# Sheet2.net
KiCad netlist of a schematic drawn in Altium Designer
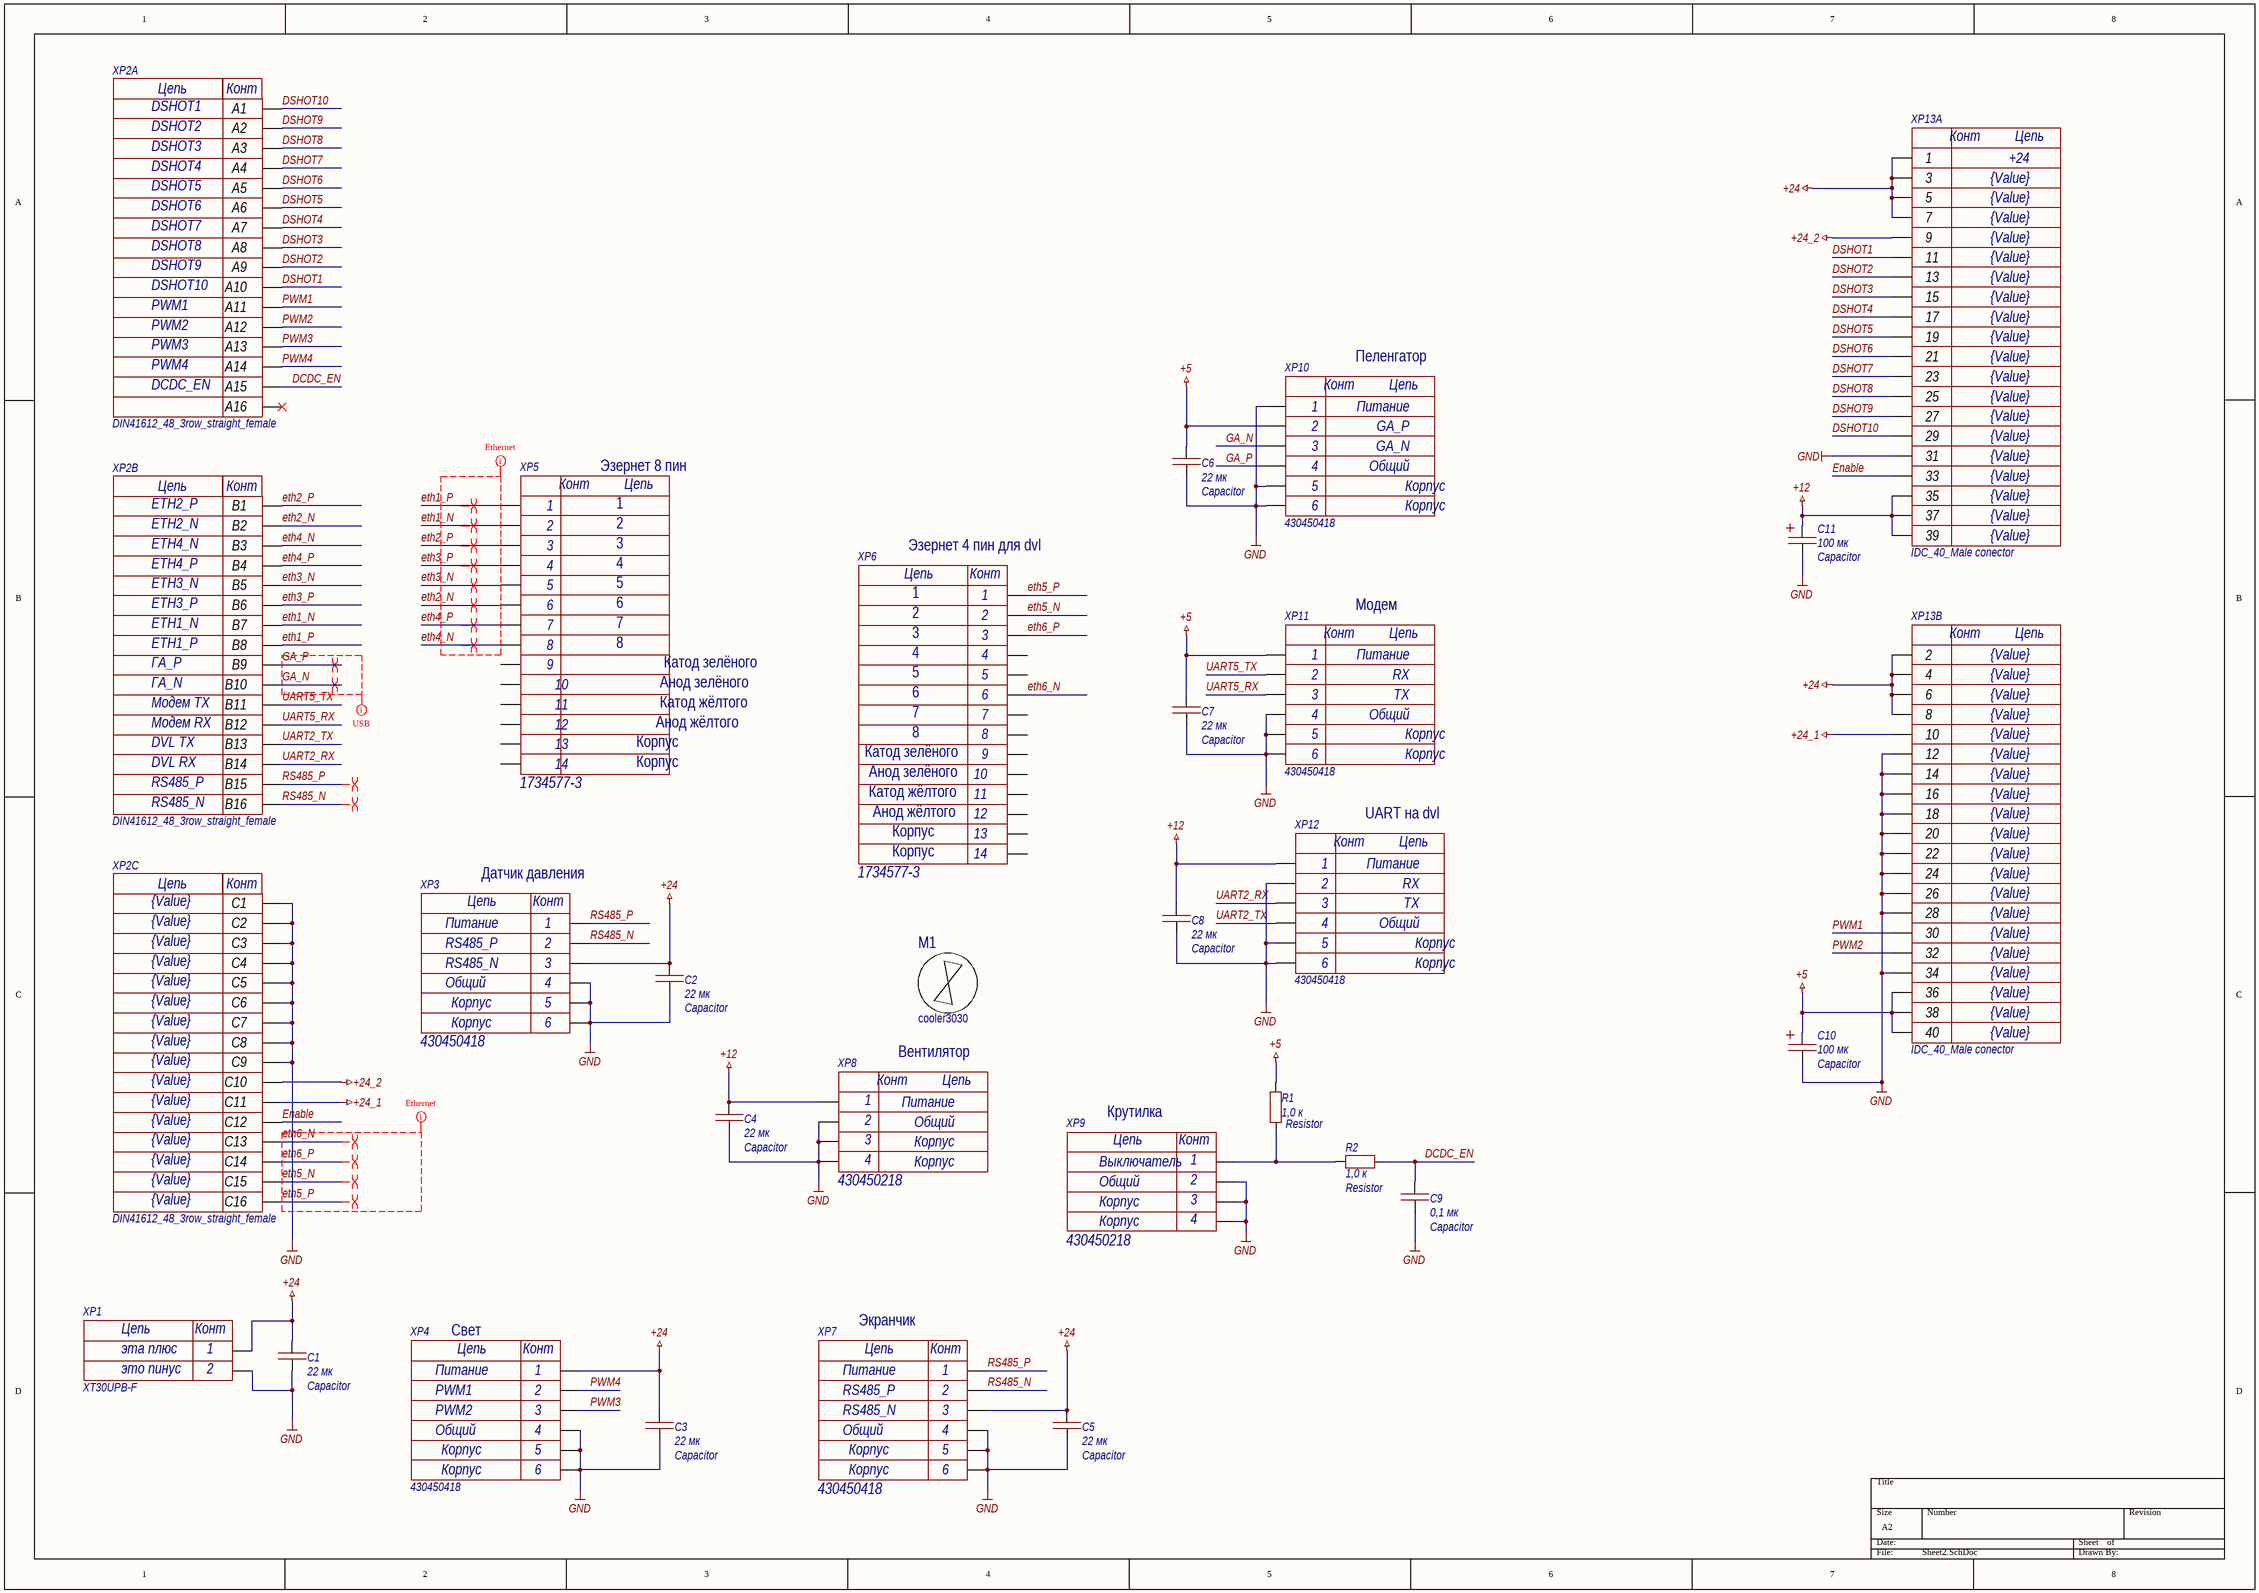
[diagram p0: Sheet2.SchDoc]

(export (version "E")
  (design (tool "Eeschema 10.0.6"))
  (components
    (comp (ref "C1")
      (value "Capacitor")
      (footprint "1210C")
      (description "Конденсатор 1210C ёмкостью 22 мк 10%, 25 В, X7R")
      (fields
        (field (name "ALTIUM_VALUE") "22 мк")
        (field (name "PART NUMBER") "Capacitor_22u_10_25V_X7R_1210C")
        (field (name "TOLERANCE") "10%")
      )
      (libsource (lib "Hydrolib") (part "Capacitor"))
    )
    (comp (ref "C2")
      (value "Capacitor")
      (footprint "1210C")
      (description "Конденсатор 1210C ёмкостью 22 мк 10%, 25 В, X7R")
      (fields
        (field (name "ALTIUM_VALUE") "22 мк")
        (field (name "PART NUMBER") "Capacitor_22u_10_25V_X7R_1210C")
        (field (name "TOLERANCE") "10%")
      )
      (libsource (lib "Hydrolib") (part "Capacitor"))
    )
    (comp (ref "C3")
      (value "Capacitor")
      (footprint "1210C")
      (description "Конденсатор 1210C ёмкостью 22 мк 10%, 25 В, X7R")
      (fields
        (field (name "ALTIUM_VALUE") "22 мк")
        (field (name "PART NUMBER") "Capacitor_22u_10_25V_X7R_1210C")
        (field (name "TOLERANCE") "10%")
      )
      (libsource (lib "Hydrolib") (part "Capacitor"))
    )
    (comp (ref "C4")
      (value "Capacitor")
      (footprint "1210C")
      (description "Конденсатор 1210C ёмкостью 22 мк 10%, 25 В, X7R")
      (fields
        (field (name "ALTIUM_VALUE") "22 мк")
        (field (name "PART NUMBER") "Capacitor_22u_10_25V_X7R_1210C")
        (field (name "TOLERANCE") "10%")
      )
      (libsource (lib "Hydrolib") (part "Capacitor"))
    )
    (comp (ref "C5")
      (value "Capacitor")
      (footprint "1210C")
      (description "Конденсатор 1210C ёмкостью 22 мк 10%, 25 В, X7R")
      (fields
        (field (name "ALTIUM_VALUE") "22 мк")
        (field (name "PART NUMBER") "Capacitor_22u_10_25V_X7R_1210C")
        (field (name "TOLERANCE") "10%")
      )
      (libsource (lib "Hydrolib") (part "Capacitor"))
    )
    (comp (ref "C6")
      (value "Capacitor")
      (footprint "1210C")
      (description "Конденсатор 1210C ёмкостью 22 мк 10%, 25 В, X7R")
      (fields
        (field (name "ALTIUM_VALUE") "22 мк")
        (field (name "PART NUMBER") "Capacitor_22u_10_25V_X7R_1210C")
        (field (name "TOLERANCE") "10%")
      )
      (libsource (lib "Hydrolib") (part "Capacitor"))
    )
    (comp (ref "C7")
      (value "Capacitor")
      (footprint "1210C")
      (description "Конденсатор 1210C ёмкостью 22 мк 10%, 25 В, X7R")
      (fields
        (field (name "ALTIUM_VALUE") "22 мк")
        (field (name "PART NUMBER") "Capacitor_22u_10_25V_X7R_1210C")
        (field (name "TOLERANCE") "10%")
      )
      (libsource (lib "Hydrolib") (part "Capacitor"))
    )
    (comp (ref "C8")
      (value "Capacitor")
      (footprint "1210C")
      (description "Конденсатор 1210C ёмкостью 22 мк 10%, 25 В, X7R")
      (fields
        (field (name "ALTIUM_VALUE") "22 мк")
        (field (name "PART NUMBER") "Capacitor_22u_10_25V_X7R_1210C")
        (field (name "TOLERANCE") "10%")
      )
      (libsource (lib "Hydrolib") (part "Capacitor"))
    )
    (comp (ref "C9")
      (value "Capacitor")
      (footprint "0603C")
      (description "Конденсатор 0603C ёмкостью 0,1 мк 10%, 50 В, X7R")
      (fields
        (field (name "ALTIUM_VALUE") "0,1 мк")
        (field (name "PART NUMBER") "Capacitor_0,1u_10_50V_X7R_0603C")
        (field (name "TOLERANCE") "10%")
      )
      (libsource (lib "Hydrolib") (part "Capacitor"))
    )
    (comp (ref "C10")
      (value "Capacitor")
      (footprint "ECAP_SMD_6,6x6,6")
      (description "Конденсатор алюминиевый электролитический 100мкФ 35В 20% SMD 6,6x6,6 мм")
      (fields
        (field (name "ALTIUM_VALUE") "100 мк")
        (field (name "PART NUMBER") "JCK1V101")
        (field (name "TOLERANCE") "20")
      )
      (libsource (lib "Hydrolib") (part "Capacitor_polar"))
    )
    (comp (ref "C11")
      (value "Capacitor")
      (footprint "ECAP_SMD_6,6x6,6")
      (description "Конденсатор алюминиевый электролитический 100мкФ 35В 20% SMD 6,6x6,6 мм")
      (fields
        (field (name "ALTIUM_VALUE") "100 мк")
        (field (name "PART NUMBER") "JCK1V101")
        (field (name "TOLERANCE") "20")
      )
      (libsource (lib "Hydrolib") (part "Capacitor_polar"))
    )
    (comp (ref "M1")
      (value "cooler3030")
      (footprint "cooler3030")
      (description "вентилятор 30*30 с дыркой на плате")
      (libsource (lib "Hydrolib") (part "cooler4040"))
    )
    (comp (ref "R1")
      (value "Resistor")
      (footprint "0603R")
      (description "Резистор номиналом 1,0 кОм 1%")
      (fields
        (field (name "ALTIUM_VALUE") "1,0 к")
        (field (name "PART NUMBER") "Resistor_1.0k_1_0603")
        (field (name "TOLERANCE") "1%")
      )
      (libsource (lib "Hydrolib") (part "Resistor"))
    )
    (comp (ref "R2")
      (value "Resistor")
      (footprint "0603R")
      (description "Резистор номиналом 1,0 кОм 1%")
      (fields
        (field (name "ALTIUM_VALUE") "1,0 к")
        (field (name "PART NUMBER") "Resistor_1.0k_1_0603")
        (field (name "TOLERANCE") "1%")
      )
      (libsource (lib "") (part "Resistor_1"))
    )
    (comp (ref "XP1")
      (value "XT30UPB-F")
      (footprint "XT30UPB-F")
      (description "30 А (15 продолжительно), прямая мать")
      (fields (field (name "VALUE2") "это пинус") (field (name "VALUE1") "эта плюс"))
      (libsource (lib "Hydrolib") (part "Polar_Conn"))
    )
    (comp (ref "XP2")
      (value "DIN41612_48_3row_straight_female")
      (footprint "DIN41612_48_3row_straight_female")
      (fields
        (field (name "PARAMETER 14") "DCDC_EN")
        (field (name "PARAMETER 16") "{Value}")
        (field (name "PARAMETER 15") "PWM4")
        (field (name "PARAMETER 12") "DSHOT7")
        (field (name "PARAMETER 13") "DSHOT5")
        (field (name "PARAMETER 11") "DSHOT6")
        (field (name "PARAMETER 10") "DSHOT4")
        (field (name "PARAMETER 9") "DSHOT3")
        (field (name "PARAMETER 8") "DSHOT2")
        (field (name "PARAMETER 5") "DSHOT1")
        (field (name "PARAMETER 6") "PWM2")
        (field (name "PARAMETER 7") "PWM3")
        (field (name "PARAMETER 4") "DSHOT10")
        (field (name "PARAMETER 3") "DSHOT9")
        (field (name "PARAMETER 2") "DSHOT8")
        (field (name "PARAMETER 1") "PWM1")
      )
      (libsource (lib "Hydrolib") (part "Conn_48pin_3row"))
    )
    (comp (ref "XP3")
      (value "430450418")
      (footprint "MOLEX_430450418")
      (description "Разъем типа провод-плата, 3 мм, 4 контакт(-ов), Штыревой Разъем, для поверностного монтажа")
      (fields
        (field (name "VALUE1") "Питание")
        (field (name "VALUE2") "RS485_P")
        (field (name "VALUE3") "RS485_N")
        (field (name "VALUE4") "Общий")
        (field (name "PART NUMBER") "Molex_430450418")
      )
      (libsource (lib "Hydrolib") (part "Molex_430450415"))
    )
    (comp (ref "XP4")
      (value "430450418")
      (footprint "MOLEX_430450418")
      (description "Разъем типа провод-плата, 3 мм, 4 контакт(-ов), Штыревой Разъем, для поверностного монтажа")
      (fields
        (field (name "VALUE1") "Питание")
        (field (name "VALUE2") "PWM1")
        (field (name "VALUE3") "PWM2")
        (field (name "VALUE4") "Общий")
        (field (name "PART NUMBER") "Molex_430450418")
      )
      (libsource (lib "Hydrolib") (part "Molex_430450415"))
    )
    (comp (ref "XP5")
      (value "1734577-3")
      (footprint "1-1734577-3-rj45-8p8c")
      (description "Модульный разъем, Cat3, RJ45, Гнездо, 8 контакт(-ов), 8 вывод(-ов), 1 порт(-ов)")
      (fields (field (name "PART NUMBER") "1-1734577-3-rj45-8p8c"))
      (libsource (lib "") (part "1-1734577-3-rj45-8p8c_1"))
    )
    (comp (ref "XP6")
      (value "1734577-3")
      (footprint "1-1734577-3-rj45-8p8c")
      (description "Модульный разъем, Cat3, RJ45, Гнездо, 8 контакт(-ов), 8 вывод(-ов), 1 порт(-ов)")
      (fields (field (name "PART NUMBER") "1-1734577-3-rj45-8p8c"))
      (libsource (lib "Hydrolib") (part "1-1734577-3-rj45-8p8c"))
    )
    (comp (ref "XP7")
      (value "430450418")
      (footprint "MOLEX_430450418")
      (description "Разъем типа провод-плата, 3 мм, 4 контакт(-ов), Штыревой Разъем, для поверностного монтажа")
      (fields
        (field (name "VALUE1") "Питание")
        (field (name "VALUE2") "RS485_P")
        (field (name "VALUE3") "RS485_N")
        (field (name "VALUE4") "Общий")
        (field (name "PART NUMBER") "Molex_430450418")
      )
      (libsource (lib "Hydrolib") (part "Molex_430450415"))
    )
    (comp (ref "XP8")
      (value "430450218")
      (footprint "Molex_430450218")
      (fields
        (field (name "VALUE3") "Корпус")
        (field (name "VALUE2") "Общий")
        (field (name "VALUE4") "Корпус")
        (field (name "VALUE1") "Питание")
        (field (name "PART NUMBER") "Molex_430450218")
      )
      (libsource (lib "Hydrolib") (part "Molex_430450218"))
    )
    (comp (ref "XP9")
      (value "430450218")
      (footprint "Molex_430450218")
      (fields
        (field (name "VALUE3") "Корпус")
        (field (name "VALUE2") "Общий")
        (field (name "VALUE4") "Корпус")
        (field (name "VALUE1") "Выключатель")
        (field (name "PART NUMBER") "Molex_430450218")
      )
      (libsource (lib "Hydrolib") (part "Molex_430450218"))
    )
    (comp (ref "XP10")
      (value "430450418")
      (footprint "MOLEX_430450418")
      (description "Разъем типа провод-плата, 3 мм, 4 контакт(-ов), Штыревой Разъем, для поверностного монтажа")
      (fields
        (field (name "VALUE1") "Питание")
        (field (name "VALUE2") "GA_P")
        (field (name "VALUE3") "GA_N")
        (field (name "VALUE4") "Общий")
        (field (name "PART NUMBER") "Molex_430450418")
      )
      (libsource (lib "") (part "Molex_430450415_1"))
    )
    (comp (ref "XP11")
      (value "430450418")
      (footprint "MOLEX_430450418")
      (description "Разъем типа провод-плата, 3 мм, 4 контакт(-ов), Штыревой Разъем, для поверностного монтажа")
      (fields
        (field (name "VALUE1") "Питание")
        (field (name "VALUE2") "RX")
        (field (name "VALUE3") "TX")
        (field (name "VALUE4") "Общий")
        (field (name "PART NUMBER") "Molex_430450418")
      )
      (libsource (lib "") (part "Molex_430450415_1"))
    )
    (comp (ref "XP12")
      (value "430450418")
      (footprint "MOLEX_430450418")
      (description "Разъем типа провод-плата, 3 мм, 4 контакт(-ов), Штыревой Разъем, для поверностного монтажа")
      (fields
        (field (name "VALUE1") "Питание")
        (field (name "VALUE2") "RX")
        (field (name "VALUE3") "TX")
        (field (name "VALUE4") "Общий")
        (field (name "PART NUMBER") "Molex_430450418")
      )
      (libsource (lib "") (part "Molex_430450415_1"))
    )
    (comp (ref "XP13")
      (value "IDC_40_Male conector")
      (footprint "IDC_40_Male conector")
      (description "IDC 40-пиновый разъём прямая вилка")
      (fields
        (field (name "VALUE17") "{Value}")
        (field (name "VALUE20") "{Value}")
        (field (name "VALUE19") "{Value}")
        (field (name "VALUE18") "{Value}")
        (field (name "VALUE16") "{Value}")
        (field (name "VALUE15") "{Value}")
        (field (name "VALUE14") "{Value}")
        (field (name "VALUE13") "{Value}")
        (field (name "VALUE12") "{Value}")
        (field (name "VALUE11") "{Value}")
        (field (name "VALUE10") "{Value}")
        (field (name "VALUE9") "{Value}")
        (field (name "VALUE8") "{Value}")
        (field (name "VALUE7") "{Value}")
        (field (name "VALUE6") "{Value}")
        (field (name "VALUE5") "{Value}")
        (field (name "VALUE4") "{Value}")
        (field (name "VALUE3") "{Value}")
        (field (name "VALUE2") "{Value}")
        (field (name "VALUE1") "{Value}")
      )
      (libsource (lib "Hydrolib") (part "Conn_40pin_double"))
    )
  )
  (nets
    (net (code "1") (name "+5") (class "Default")
      (node (ref "C10") (pin "1") (pinfunction "1_1") (pintype "passive"))
      (node (ref "C6") (pin "2") (pinfunction "2_2") (pintype "passive"))
      (node (ref "C7") (pin "2") (pinfunction "2_2") (pintype "passive"))
      (node (ref "R1") (pin "1") (pinfunction "1_1") (pintype "passive"))
      (node (ref "XP10") (pin "2") (pinfunction "2_2") (pintype "passive"))
      (node (ref "XP11") (pin "1") (pinfunction "1_1") (pintype "passive"))
      (node (ref "XP13") (pin "36") (pinfunction "36_36") (pintype "passive"))
      (node (ref "XP13") (pin "38") (pinfunction "38_38") (pintype "passive"))
      (node (ref "XP13") (pin "40") (pinfunction "40_40") (pintype "passive"))
    )
    (net (code "2") (name "+12") (class "Default")
      (node (ref "C11") (pin "1") (pinfunction "1_1") (pintype "passive"))
      (node (ref "C4") (pin "2") (pinfunction "2_2") (pintype "passive"))
      (node (ref "C8") (pin "2") (pinfunction "2_2") (pintype "passive"))
      (node (ref "XP12") (pin "1") (pinfunction "1_1") (pintype "passive"))
      (node (ref "XP13") (pin "35") (pinfunction "35_35") (pintype "passive"))
      (node (ref "XP13") (pin "37") (pinfunction "37_37") (pintype "passive"))
      (node (ref "XP13") (pin "39") (pinfunction "39_39") (pintype "passive"))
      (node (ref "XP8") (pin "1") (pinfunction "1_1") (pintype "passive"))
    )
    (net (code "3") (name "+24") (class "Default")
      (node (ref "C1") (pin "2") (pinfunction "2_2") (pintype "passive"))
      (node (ref "C2") (pin "2") (pinfunction "2_2") (pintype "passive"))
      (node (ref "C3") (pin "2") (pinfunction "2_2") (pintype "passive"))
      (node (ref "C5") (pin "2") (pinfunction "2_2") (pintype "passive"))
      (node (ref "XP1") (pin "P") (pinfunction "P_P") (pintype "passive"))
      (node (ref "XP13") (pin "1") (pinfunction "1_1") (pintype "passive"))
      (node (ref "XP13") (pin "2") (pinfunction "2_2") (pintype "passive"))
      (node (ref "XP13") (pin "3") (pinfunction "3_3") (pintype "passive"))
      (node (ref "XP13") (pin "4") (pinfunction "4_4") (pintype "passive"))
      (node (ref "XP13") (pin "5") (pinfunction "5_5") (pintype "passive"))
      (node (ref "XP13") (pin "6") (pinfunction "6_6") (pintype "passive"))
      (node (ref "XP13") (pin "7") (pinfunction "7_7") (pintype "passive"))
      (node (ref "XP13") (pin "8") (pinfunction "8_8") (pintype "passive"))
      (node (ref "XP3") (pin "3") (pinfunction "3_3") (pintype "passive"))
      (node (ref "XP4") (pin "1") (pinfunction "1_1") (pintype "passive"))
      (node (ref "XP7") (pin "3") (pinfunction "3_3") (pintype "passive"))
    )
    (net (code "4") (name "+24_1") (class "Default")
      (node (ref "XP13") (pin "10") (pinfunction "10_10") (pintype "passive"))
      (node (ref "XP2") (pin "C11") (pinfunction "C11_C11") (pintype "passive"))
    )
    (net (code "5") (name "+24_2") (class "Default")
      (node (ref "XP13") (pin "9") (pinfunction "9_9") (pintype "passive"))
      (node (ref "XP2") (pin "C10") (pinfunction "C10_C10") (pintype "passive"))
    )
    (net (code "6") (name "/DCDC_EN") (class "Default")
      (node (ref "C9") (pin "2") (pinfunction "2_2") (pintype "passive"))
      (node (ref "R2") (pin "1") (pinfunction "1_1") (pintype "passive"))
      (node (ref "XP2") (pin "A15") (pinfunction "A15_A15") (pintype "passive"))
    )
    (net (code "7") (name "/DSHOT1") (class "Default")
      (node (ref "XP13") (pin "11") (pinfunction "11_11") (pintype "passive"))
      (node (ref "XP2") (pin "A10") (pinfunction "A10_A10") (pintype "passive"))
    )
    (net (code "8") (name "/DSHOT2") (class "Default")
      (node (ref "XP13") (pin "13") (pinfunction "13_13") (pintype "passive"))
      (node (ref "XP2") (pin "A9") (pinfunction "A9_A9") (pintype "passive"))
    )
    (net (code "9") (name "/DSHOT3") (class "Default")
      (node (ref "XP13") (pin "15") (pinfunction "15_15") (pintype "passive"))
      (node (ref "XP2") (pin "A8") (pinfunction "A8_A8") (pintype "passive"))
    )
    (net (code "10") (name "/DSHOT4") (class "Default")
      (node (ref "XP13") (pin "17") (pinfunction "17_17") (pintype "passive"))
      (node (ref "XP2") (pin "A7") (pinfunction "A7_A7") (pintype "passive"))
    )
    (net (code "11") (name "/DSHOT5") (class "Default")
      (node (ref "XP13") (pin "19") (pinfunction "19_19") (pintype "passive"))
      (node (ref "XP2") (pin "A6") (pinfunction "A6_A6") (pintype "passive"))
    )
    (net (code "12") (name "/DSHOT6") (class "Default")
      (node (ref "XP13") (pin "21") (pinfunction "21_21") (pintype "passive"))
      (node (ref "XP2") (pin "A5") (pinfunction "A5_A5") (pintype "passive"))
    )
    (net (code "13") (name "/DSHOT7") (class "Default")
      (node (ref "XP13") (pin "23") (pinfunction "23_23") (pintype "passive"))
      (node (ref "XP2") (pin "A4") (pinfunction "A4_A4") (pintype "passive"))
    )
    (net (code "14") (name "/DSHOT8") (class "Default")
      (node (ref "XP13") (pin "25") (pinfunction "25_25") (pintype "passive"))
      (node (ref "XP2") (pin "A3") (pinfunction "A3_A3") (pintype "passive"))
    )
    (net (code "15") (name "/DSHOT9") (class "Default")
      (node (ref "XP13") (pin "27") (pinfunction "27_27") (pintype "passive"))
      (node (ref "XP2") (pin "A2") (pinfunction "A2_A2") (pintype "passive"))
    )
    (net (code "16") (name "/DSHOT10") (class "Default")
      (node (ref "XP13") (pin "29") (pinfunction "29_29") (pintype "passive"))
      (node (ref "XP2") (pin "A1") (pinfunction "A1_A1") (pintype "passive"))
    )
    (net (code "17") (name "/Enable") (class "Default")
      (node (ref "XP13") (pin "33") (pinfunction "33_33") (pintype "passive"))
      (node (ref "XP2") (pin "C12") (pinfunction "C12_C12") (pintype "passive"))
    )
    (net (code "18") (name "/GA_N") (class "Default")
      (node (ref "XP10") (pin "3") (pinfunction "3_3") (pintype "passive"))
      (node (ref "XP2") (pin "B10") (pinfunction "B10_B10") (pintype "passive"))
    )
    (net (code "19") (name "/GA_P") (class "Default")
      (node (ref "XP10") (pin "4") (pinfunction "4_4") (pintype "passive"))
      (node (ref "XP2") (pin "B9") (pinfunction "B9_B9") (pintype "passive"))
    )
    (net (code "20") (name "/PWM1") (class "Default")
      (node (ref "XP13") (pin "30") (pinfunction "30_30") (pintype "passive"))
      (node (ref "XP2") (pin "A11") (pinfunction "A11_A11") (pintype "passive"))
    )
    (net (code "21") (name "/PWM2") (class "Default")
      (node (ref "XP13") (pin "32") (pinfunction "32_32") (pintype "passive"))
      (node (ref "XP2") (pin "A12") (pinfunction "A12_A12") (pintype "passive"))
    )
    (net (code "22") (name "/PWM3") (class "Default")
      (node (ref "XP2") (pin "A13") (pinfunction "A13_A13") (pintype "passive"))
      (node (ref "XP4") (pin "3") (pinfunction "3_3") (pintype "passive"))
    )
    (net (code "23") (name "/PWM4") (class "Default")
      (node (ref "XP2") (pin "A14") (pinfunction "A14_A14") (pintype "passive"))
      (node (ref "XP4") (pin "2") (pinfunction "2_2") (pintype "passive"))
    )
    (net (code "24") (name "/RS485_N") (class "Default")
      (node (ref "XP2") (pin "B16") (pinfunction "B16_B16") (pintype "passive"))
      (node (ref "XP3") (pin "2") (pinfunction "2_2") (pintype "passive"))
      (node (ref "XP7") (pin "2") (pinfunction "2_2") (pintype "passive"))
    )
    (net (code "25") (name "/RS485_P") (class "Default")
      (node (ref "XP2") (pin "B15") (pinfunction "B15_B15") (pintype "passive"))
      (node (ref "XP3") (pin "1") (pinfunction "1_1") (pintype "passive"))
      (node (ref "XP7") (pin "1") (pinfunction "1_1") (pintype "passive"))
    )
    (net (code "26") (name "/UART2_RX") (class "Default")
      (node (ref "XP12") (pin "3") (pinfunction "3_3") (pintype "passive"))
      (node (ref "XP2") (pin "B14") (pinfunction "B14_B14") (pintype "passive"))
    )
    (net (code "27") (name "/UART2_TX") (class "Default")
      (node (ref "XP12") (pin "4") (pinfunction "4_4") (pintype "passive"))
      (node (ref "XP2") (pin "B13") (pinfunction "B13_B13") (pintype "passive"))
    )
    (net (code "28") (name "/UART5_RX") (class "Default")
      (node (ref "XP11") (pin "3") (pinfunction "3_3") (pintype "passive"))
      (node (ref "XP2") (pin "B12") (pinfunction "B12_B12") (pintype "passive"))
    )
    (net (code "29") (name "/UART5_TX") (class "Default")
      (node (ref "XP11") (pin "2") (pinfunction "2_2") (pintype "passive"))
      (node (ref "XP2") (pin "B11") (pinfunction "B11_B11") (pintype "passive"))
    )
    (net (code "30") (name "/eth1_N") (class "Default")
      (node (ref "XP2") (pin "B7") (pinfunction "B7_B7") (pintype "passive"))
      (node (ref "XP5") (pin "2") (pinfunction "2_2") (pintype "passive"))
    )
    (net (code "31") (name "/eth1_P") (class "Default")
      (node (ref "XP2") (pin "B8") (pinfunction "B8_B8") (pintype "passive"))
      (node (ref "XP5") (pin "1") (pinfunction "1_1") (pintype "passive"))
    )
    (net (code "32") (name "/eth2_N") (class "Default")
      (node (ref "XP2") (pin "B2") (pinfunction "B2_B2") (pintype "passive"))
      (node (ref "XP5") (pin "6") (pinfunction "6_6") (pintype "passive"))
    )
    (net (code "33") (name "/eth2_P") (class "Default")
      (node (ref "XP2") (pin "B1") (pinfunction "B1_B1") (pintype "passive"))
      (node (ref "XP5") (pin "3") (pinfunction "3_3") (pintype "passive"))
    )
    (net (code "34") (name "/eth3_N") (class "Default")
      (node (ref "XP2") (pin "B5") (pinfunction "B5_B5") (pintype "passive"))
      (node (ref "XP5") (pin "5") (pinfunction "5_5") (pintype "passive"))
    )
    (net (code "35") (name "/eth3_P") (class "Default")
      (node (ref "XP2") (pin "B6") (pinfunction "B6_B6") (pintype "passive"))
      (node (ref "XP5") (pin "4") (pinfunction "4_4") (pintype "passive"))
    )
    (net (code "36") (name "/eth4_N") (class "Default")
      (node (ref "XP2") (pin "B3") (pinfunction "B3_B3") (pintype "passive"))
      (node (ref "XP5") (pin "8") (pinfunction "8_8") (pintype "passive"))
    )
    (net (code "37") (name "/eth4_P") (class "Default")
      (node (ref "XP2") (pin "B4") (pinfunction "B4_B4") (pintype "passive"))
      (node (ref "XP5") (pin "7") (pinfunction "7_7") (pintype "passive"))
    )
    (net (code "38") (name "/eth5_N") (class "Default")
      (node (ref "XP2") (pin "C15") (pinfunction "C15_C15") (pintype "passive"))
      (node (ref "XP6") (pin "2") (pinfunction "2_2") (pintype "passive"))
    )
    (net (code "39") (name "/eth5_P") (class "Default")
      (node (ref "XP2") (pin "C16") (pinfunction "C16_C16") (pintype "passive"))
      (node (ref "XP6") (pin "1") (pinfunction "1_1") (pintype "passive"))
    )
    (net (code "40") (name "/eth6_N") (class "Default")
      (node (ref "XP2") (pin "C13") (pinfunction "C13_C13") (pintype "passive"))
      (node (ref "XP6") (pin "6") (pinfunction "6_6") (pintype "passive"))
    )
    (net (code "41") (name "/eth6_P") (class "Default")
      (node (ref "XP2") (pin "C14") (pinfunction "C14_C14") (pintype "passive"))
      (node (ref "XP6") (pin "3") (pinfunction "3_3") (pintype "passive"))
    )
    (net (code "42") (name "GND") (class "Default")
      (node (ref "C1") (pin "1") (pinfunction "1_1") (pintype "passive"))
      (node (ref "C10") (pin "2") (pinfunction "2_2") (pintype "passive"))
      (node (ref "C11") (pin "2") (pinfunction "2_2") (pintype "passive"))
      (node (ref "C2") (pin "1") (pinfunction "1_1") (pintype "passive"))
      (node (ref "C3") (pin "1") (pinfunction "1_1") (pintype "passive"))
      (node (ref "C4") (pin "1") (pinfunction "1_1") (pintype "passive"))
      (node (ref "C5") (pin "1") (pinfunction "1_1") (pintype "passive"))
      (node (ref "C6") (pin "1") (pinfunction "1_1") (pintype "passive"))
      (node (ref "C7") (pin "1") (pinfunction "1_1") (pintype "passive"))
      (node (ref "C8") (pin "1") (pinfunction "1_1") (pintype "passive"))
      (node (ref "C9") (pin "1") (pinfunction "1_1") (pintype "passive"))
      (node (ref "XP1") (pin "N") (pinfunction "N_N") (pintype "passive"))
      (node (ref "XP10") (pin "0") (pinfunction "0_0") (pintype "passive"))
      (node (ref "XP10") (pin "1") (pinfunction "1_1") (pintype "passive"))
      (node (ref "XP11") (pin "0") (pinfunction "0_0") (pintype "passive"))
      (node (ref "XP11") (pin "4") (pinfunction "4_4") (pintype "passive"))
      (node (ref "XP12") (pin "0") (pinfunction "0_0") (pintype "passive"))
      (node (ref "XP12") (pin "2") (pinfunction "2_2") (pintype "passive"))
      (node (ref "XP13") (pin "12") (pinfunction "12_12") (pintype "passive"))
      (node (ref "XP13") (pin "14") (pinfunction "14_14") (pintype "passive"))
      (node (ref "XP13") (pin "16") (pinfunction "16_16") (pintype "passive"))
      (node (ref "XP13") (pin "18") (pinfunction "18_18") (pintype "passive"))
      (node (ref "XP13") (pin "20") (pinfunction "20_20") (pintype "passive"))
      (node (ref "XP13") (pin "22") (pinfunction "22_22") (pintype "passive"))
      (node (ref "XP13") (pin "24") (pinfunction "24_24") (pintype "passive"))
      (node (ref "XP13") (pin "26") (pinfunction "26_26") (pintype "passive"))
      (node (ref "XP13") (pin "28") (pinfunction "28_28") (pintype "passive"))
      (node (ref "XP13") (pin "31") (pinfunction "31_31") (pintype "passive"))
      (node (ref "XP13") (pin "34") (pinfunction "34_34") (pintype "passive"))
      (node (ref "XP2") (pin "C1") (pinfunction "C1_C1") (pintype "passive"))
      (node (ref "XP2") (pin "C2") (pinfunction "C2_C2") (pintype "passive"))
      (node (ref "XP2") (pin "C3") (pinfunction "C3_C3") (pintype "passive"))
      (node (ref "XP2") (pin "C4") (pinfunction "C4_C4") (pintype "passive"))
      (node (ref "XP2") (pin "C5") (pinfunction "C5_C5") (pintype "passive"))
      (node (ref "XP2") (pin "C6") (pinfunction "C6_C6") (pintype "passive"))
      (node (ref "XP2") (pin "C7") (pinfunction "C7_C7") (pintype "passive"))
      (node (ref "XP2") (pin "C8") (pinfunction "C8_C8") (pintype "passive"))
      (node (ref "XP2") (pin "C9") (pinfunction "C9_C9") (pintype "passive"))
      (node (ref "XP3") (pin "0") (pinfunction "0_0") (pintype "passive"))
      (node (ref "XP3") (pin "4") (pinfunction "4_4") (pintype "passive"))
      (node (ref "XP4") (pin "0") (pinfunction "0_0") (pintype "passive"))
      (node (ref "XP4") (pin "4") (pinfunction "4_4") (pintype "passive"))
      (node (ref "XP7") (pin "0") (pinfunction "0_0") (pintype "passive"))
      (node (ref "XP7") (pin "4") (pinfunction "4_4") (pintype "passive"))
      (node (ref "XP8") (pin "0") (pinfunction "0_0") (pintype "passive"))
      (node (ref "XP8") (pin "2") (pinfunction "2_2") (pintype "passive"))
      (node (ref "XP9") (pin "0") (pinfunction "0_0") (pintype "passive"))
      (node (ref "XP9") (pin "2") (pinfunction "2_2") (pintype "passive"))
    )
    (net (code "43") (name "Net-(R1-Pad2)") (class "Default")
      (node (ref "R1") (pin "2") (pinfunction "2_2") (pintype "passive"))
      (node (ref "R2") (pin "2") (pinfunction "2_2") (pintype "passive"))
      (node (ref "XP9") (pin "1") (pinfunction "1_1") (pintype "passive"))
    )
    (net (code "44") (name "unconnected-(XP2-PadA16)") (class "Default")
      (node (ref "XP2") (pin "A16") (pinfunction "A16_A16") (pintype "passive+no_connect"))
    )
    (net (code "45") (name "unconnected-(XP5-Pad9)") (class "Default")
      (node (ref "XP5") (pin "9") (pinfunction "9_9") (pintype "passive"))
    )
    (net (code "46") (name "unconnected-(XP5-Pad10)") (class "Default")
      (node (ref "XP5") (pin "10") (pinfunction "10_10") (pintype "passive"))
    )
    (net (code "47") (name "unconnected-(XP5-Pad11)") (class "Default")
      (node (ref "XP5") (pin "11") (pinfunction "11_11") (pintype "passive"))
    )
    (net (code "48") (name "unconnected-(XP5-Pad12)") (class "Default")
      (node (ref "XP5") (pin "12") (pinfunction "12_12") (pintype "passive"))
    )
    (net (code "49") (name "unconnected-(XP5-PadMH1)") (class "Default")
      (node (ref "XP5") (pin "MH1") (pinfunction "MH1_MH1") (pintype "passive"))
    )
    (net (code "50") (name "unconnected-(XP5-PadMH2)") (class "Default")
      (node (ref "XP5") (pin "MH2") (pinfunction "MH2_MH2") (pintype "passive"))
    )
    (net (code "51") (name "unconnected-(XP6-Pad4)") (class "Default")
      (node (ref "XP6") (pin "4") (pinfunction "4_4") (pintype "passive"))
    )
    (net (code "52") (name "unconnected-(XP6-Pad5)") (class "Default")
      (node (ref "XP6") (pin "5") (pinfunction "5_5") (pintype "passive"))
    )
    (net (code "53") (name "unconnected-(XP6-Pad7)") (class "Default")
      (node (ref "XP6") (pin "7") (pinfunction "7_7") (pintype "passive"))
    )
    (net (code "54") (name "unconnected-(XP6-Pad8)") (class "Default")
      (node (ref "XP6") (pin "8") (pinfunction "8_8") (pintype "passive"))
    )
    (net (code "55") (name "unconnected-(XP6-Pad9)") (class "Default")
      (node (ref "XP6") (pin "9") (pinfunction "9_9") (pintype "passive"))
    )
    (net (code "56") (name "unconnected-(XP6-Pad10)") (class "Default")
      (node (ref "XP6") (pin "10") (pinfunction "10_10") (pintype "passive"))
    )
    (net (code "57") (name "unconnected-(XP6-Pad11)") (class "Default")
      (node (ref "XP6") (pin "11") (pinfunction "11_11") (pintype "passive"))
    )
    (net (code "58") (name "unconnected-(XP6-Pad12)") (class "Default")
      (node (ref "XP6") (pin "12") (pinfunction "12_12") (pintype "passive"))
    )
    (net (code "59") (name "unconnected-(XP6-PadMH1)") (class "Default")
      (node (ref "XP6") (pin "MH1") (pinfunction "MH1_MH1") (pintype "passive"))
    )
    (net (code "60") (name "unconnected-(XP6-PadMH2)") (class "Default")
      (node (ref "XP6") (pin "MH2") (pinfunction "MH2_MH2") (pintype "passive"))
    )
  )
)
